# moire_v1_6.net
KiCad netlist of a schematic drawn in EAGLE
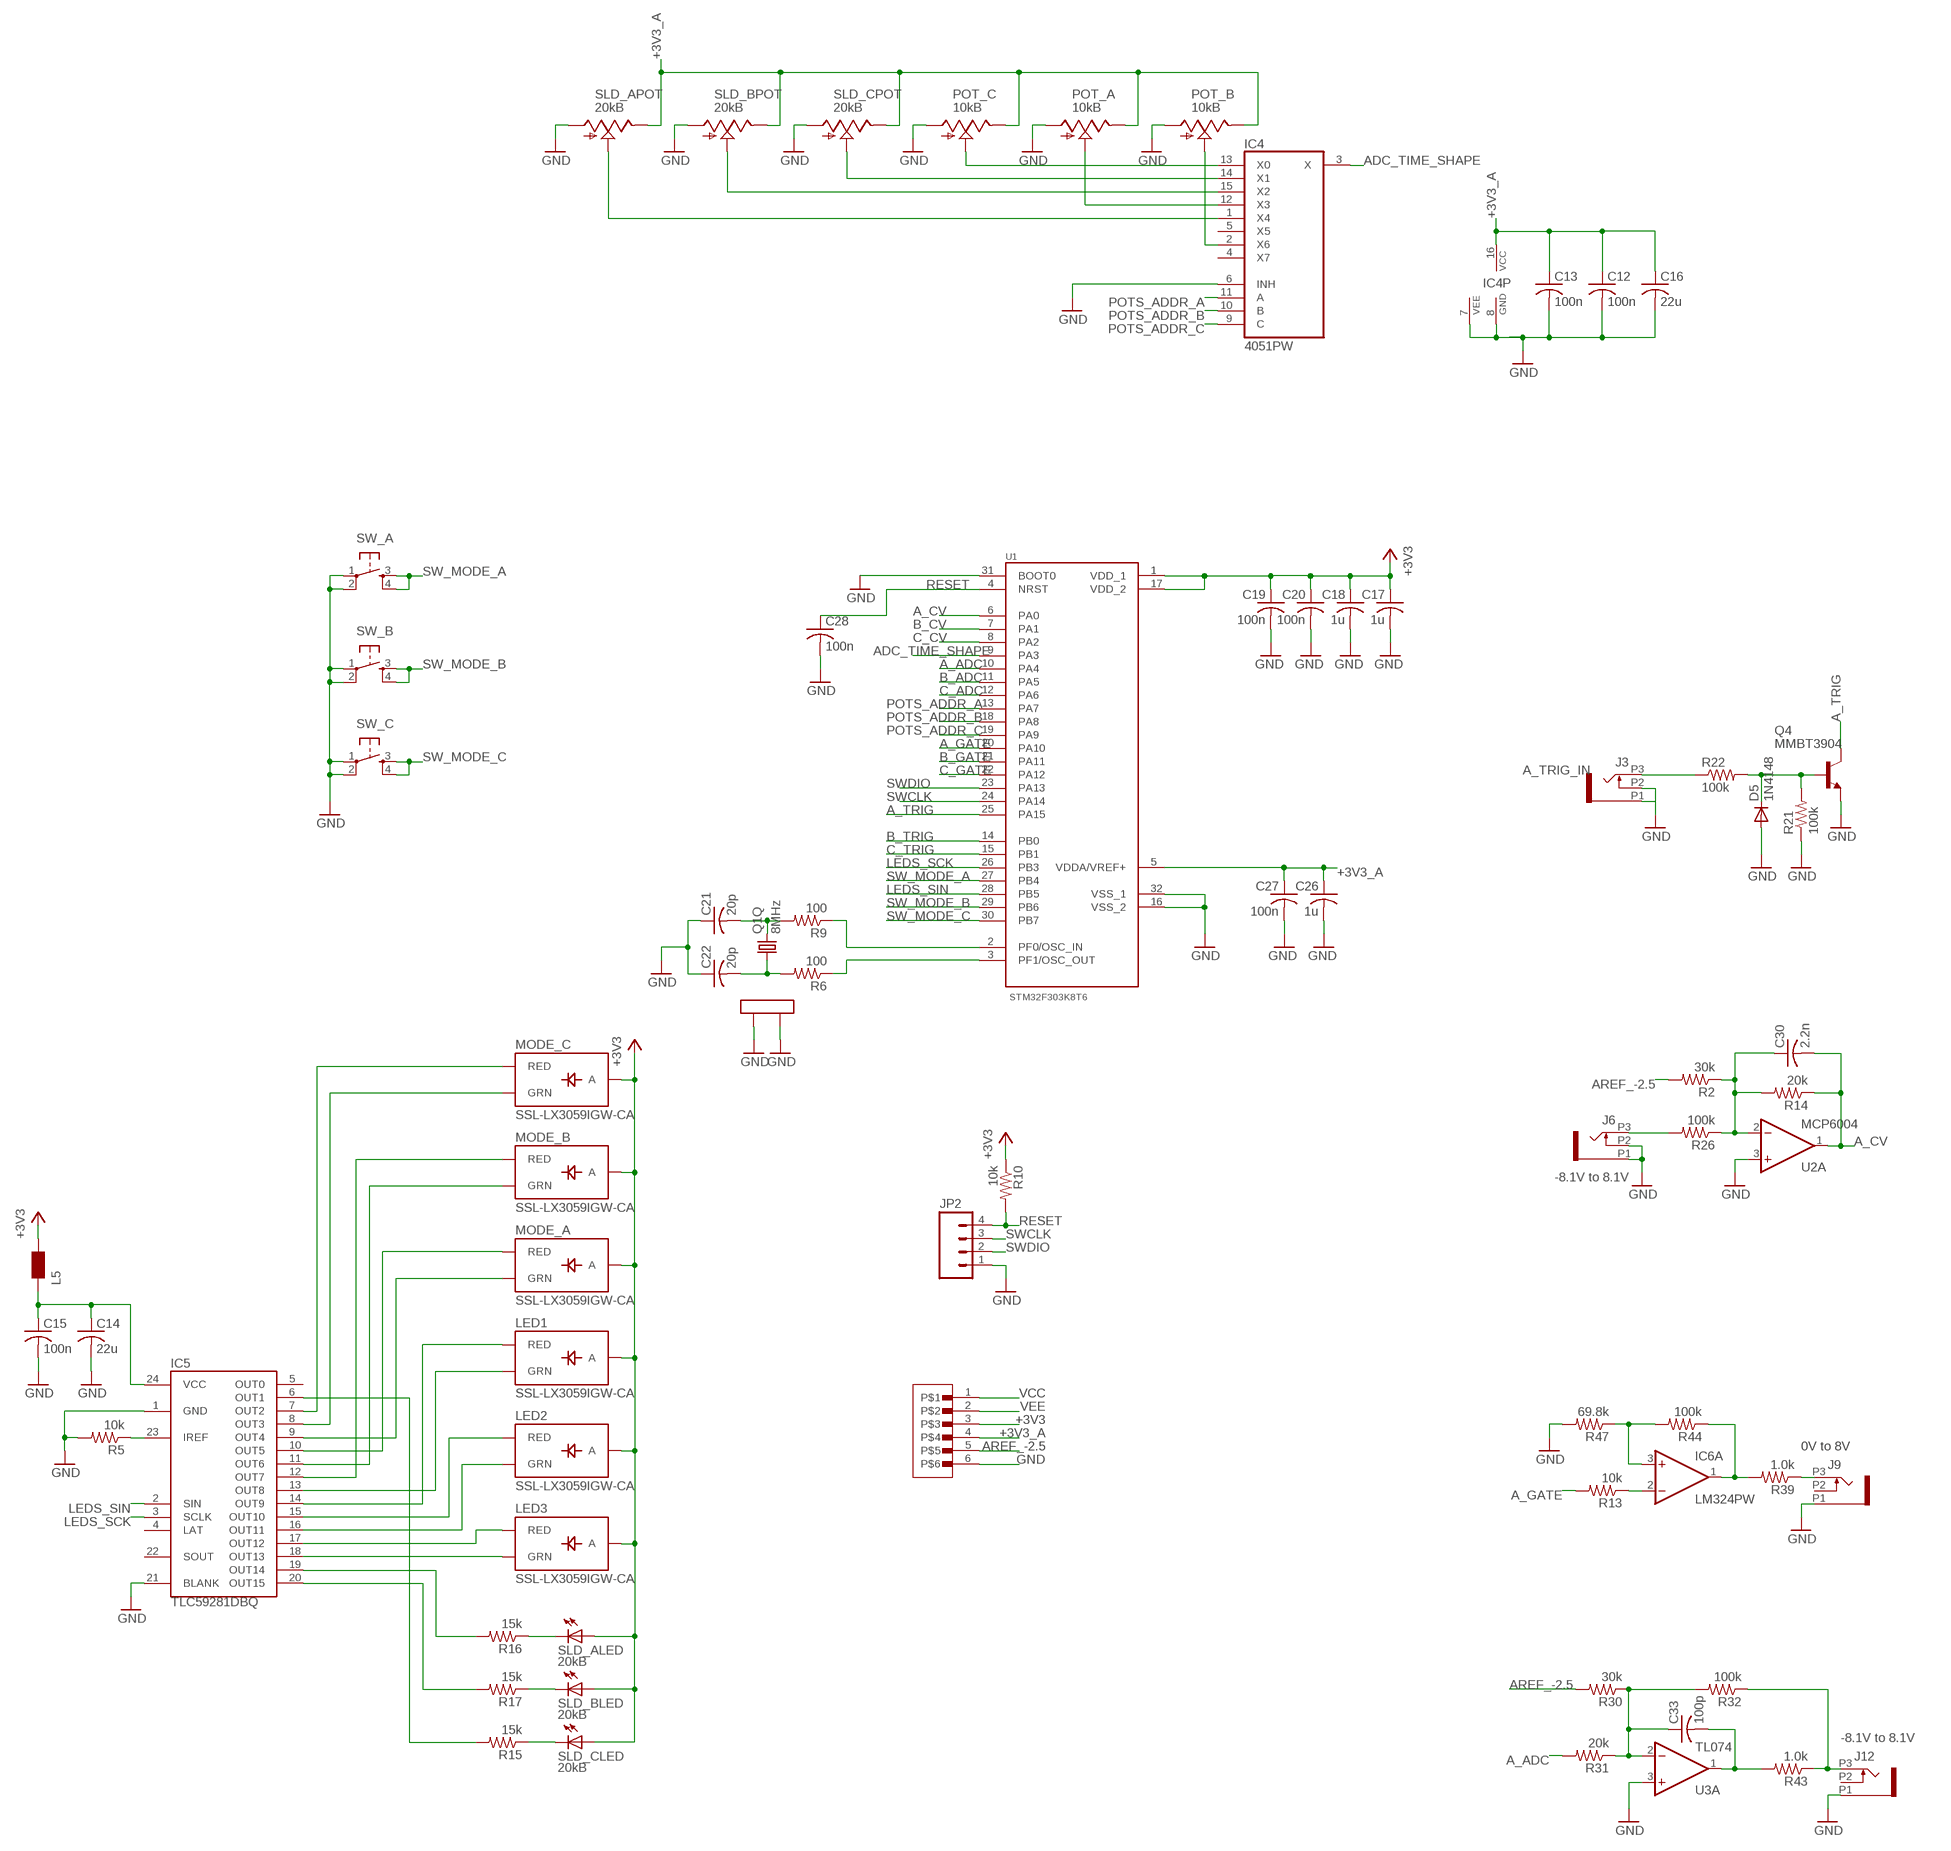
[diagram p0: schematic, sheet 1, part 1 of 2]
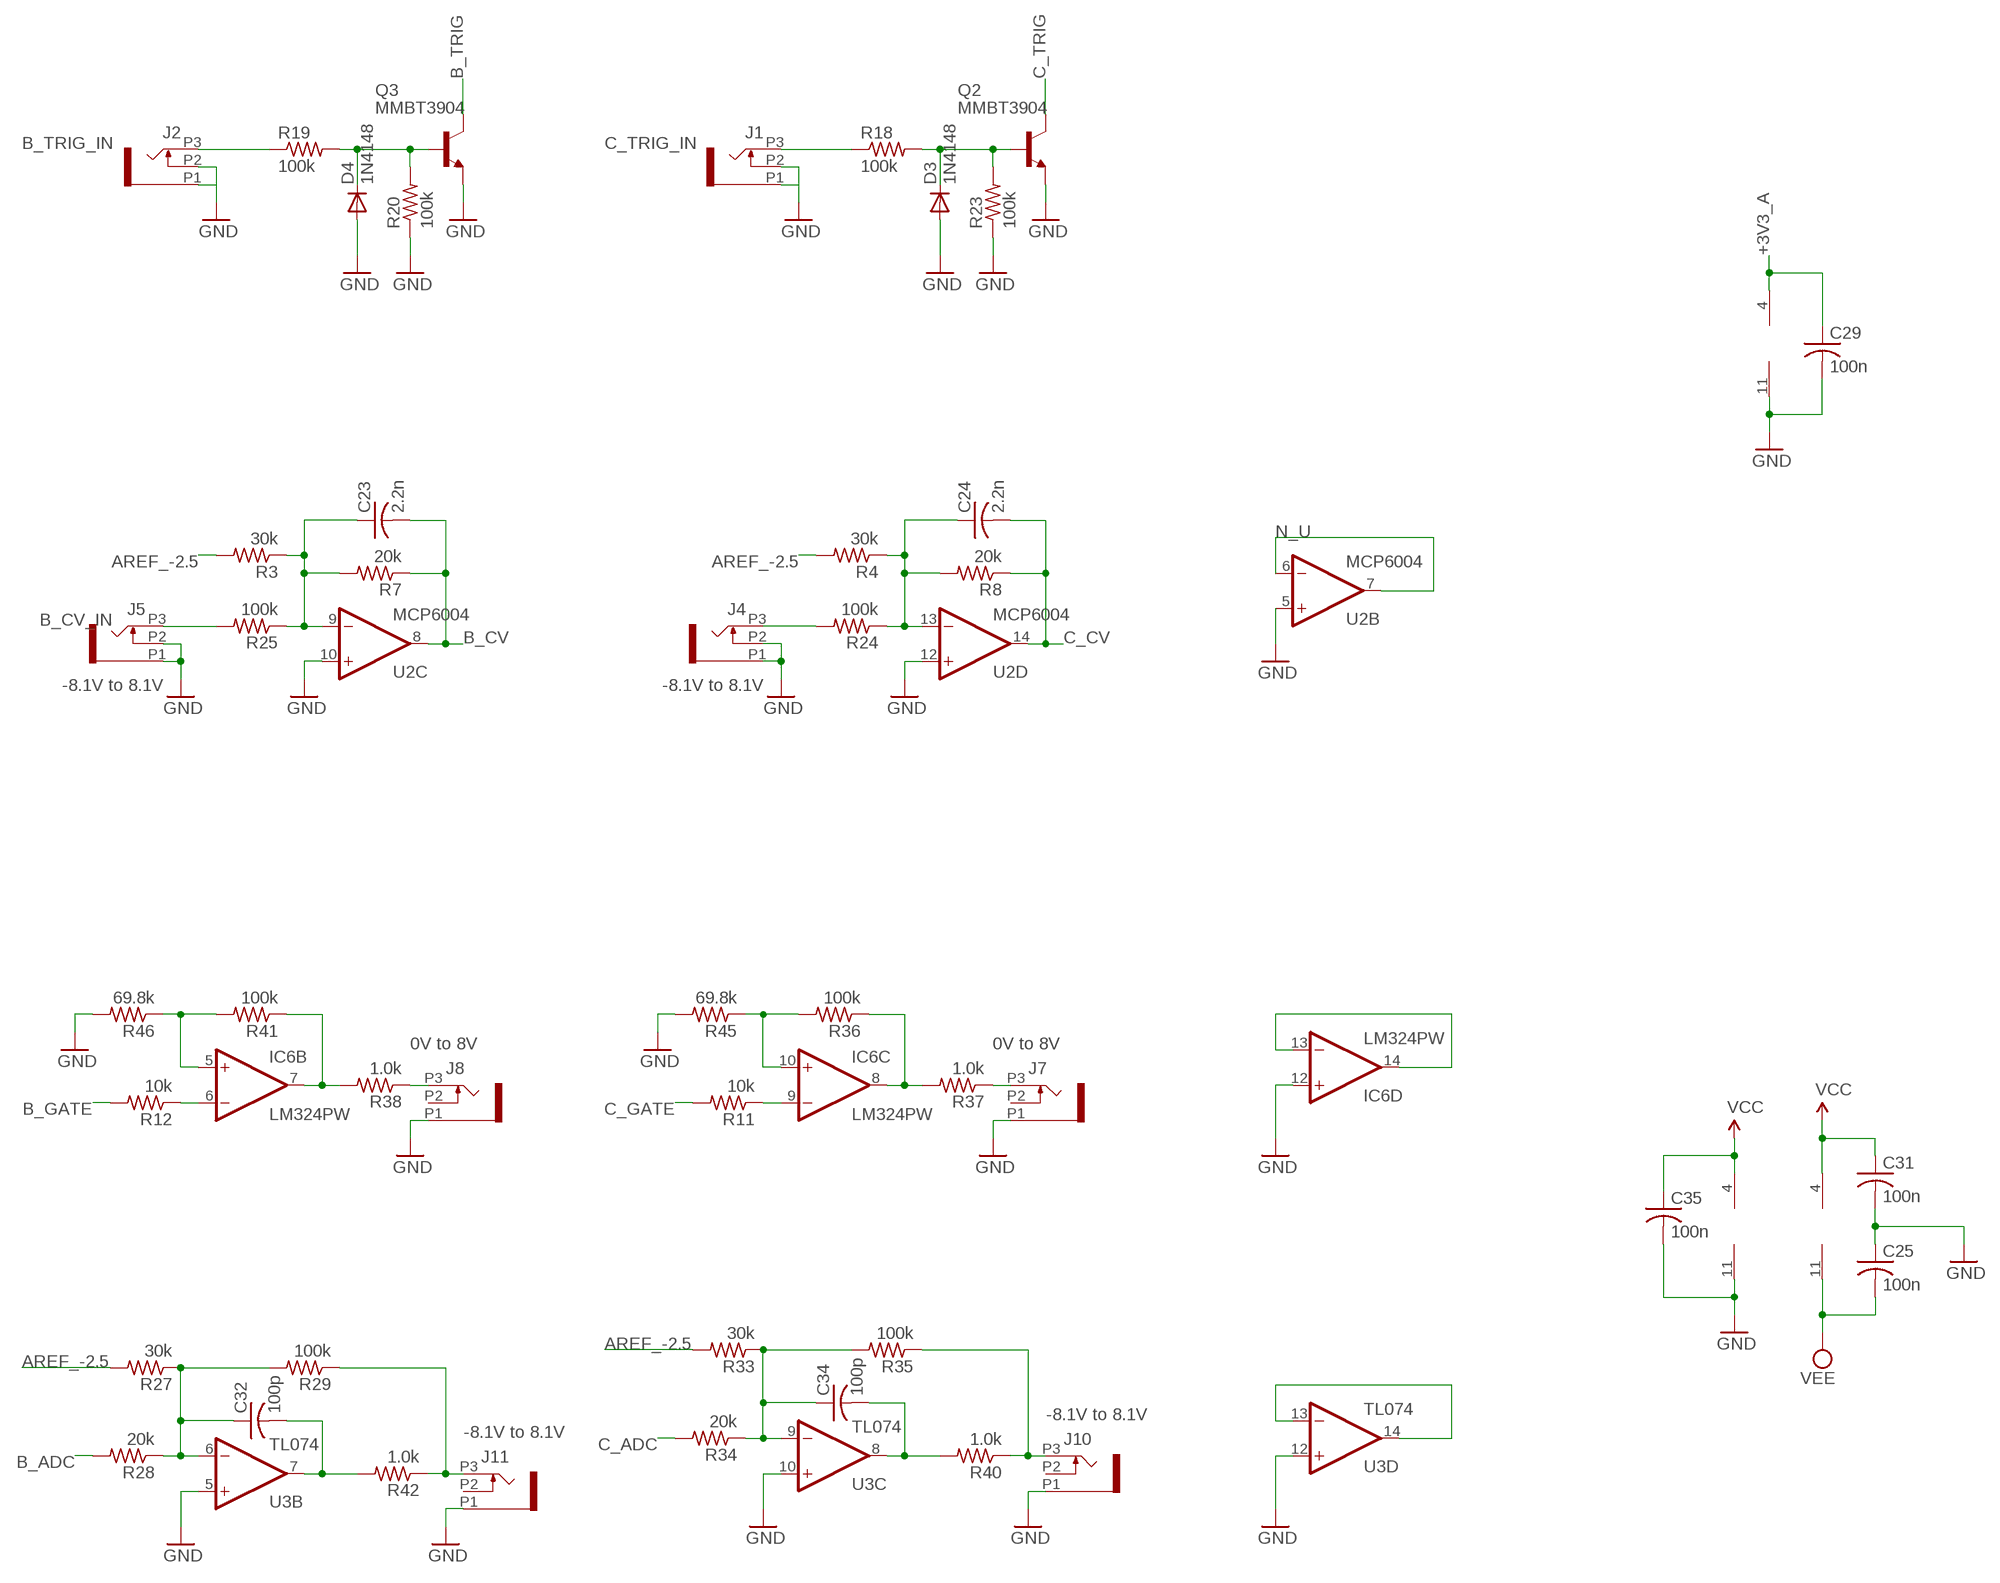
[diagram p1: schematic, sheet 1, part 2 of 2]
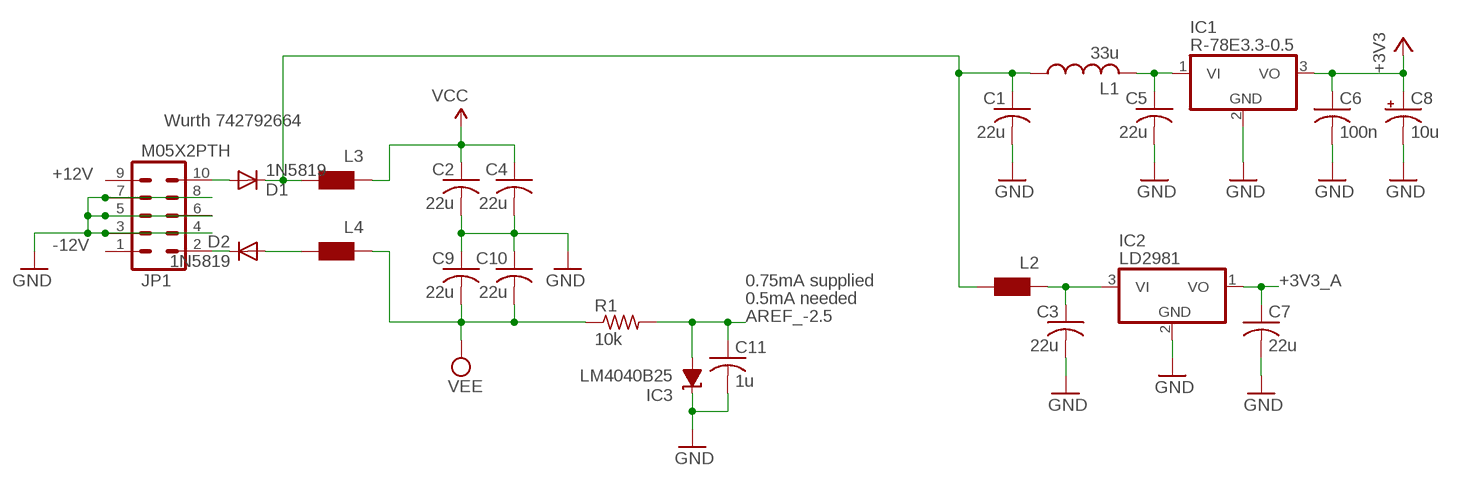
[diagram p2: schematic, sheet 2]

(export (version "E")
  (design (tool "Eeschema 10.0.6"))
  (components
    (comp (ref "C12")
      (value "100n")
      (footprint "eagle-import:RCL_C0603")
      (libsource (lib "eagle-import") (part "RCL_C-USC0603"))
    )
    (comp (ref "C13")
      (value "100n")
      (footprint "eagle-import:RCL_C0603")
      (libsource (lib "eagle-import") (part "RCL_C-USC0603"))
    )
    (comp (ref "C14")
      (value "22u")
      (footprint "eagle-import:RCL_C1206")
      (libsource (lib "eagle-import") (part "RCL_C-USC1206"))
    )
    (comp (ref "C15")
      (value "100n")
      (footprint "eagle-import:RCL_C0603")
      (libsource (lib "eagle-import") (part "RCL_C-USC0603"))
    )
    (comp (ref "C16")
      (value "22u")
      (footprint "eagle-import:RCL_C1206")
      (libsource (lib "eagle-import") (part "RCL_C-USC1206"))
    )
    (comp (ref "C17")
      (value "1u")
      (footprint "eagle-import:RCL_C0603")
      (libsource (lib "eagle-import") (part "RCL_C-USC0603"))
    )
    (comp (ref "C18")
      (value "1u")
      (footprint "eagle-import:RCL_C0603")
      (libsource (lib "eagle-import") (part "RCL_C-USC0603"))
    )
    (comp (ref "C19")
      (value "100n")
      (footprint "eagle-import:RCL_C0603")
      (libsource (lib "eagle-import") (part "RCL_C-USC0603"))
    )
    (comp (ref "C20")
      (value "100n")
      (footprint "eagle-import:RCL_C0603")
      (libsource (lib "eagle-import") (part "RCL_C-USC0603"))
    )
    (comp (ref "C21")
      (value "20p")
      (footprint "eagle-import:RCL_C0603")
      (libsource (lib "eagle-import") (part "RCL_C-USC0603"))
    )
    (comp (ref "C22")
      (value "20p")
      (footprint "eagle-import:RCL_C0603")
      (libsource (lib "eagle-import") (part "RCL_C-USC0603"))
    )
    (comp (ref "C23")
      (value "2.2n")
      (footprint "eagle-import:RCL_C0603")
      (libsource (lib "eagle-import") (part "RCL_C-USC0603"))
    )
    (comp (ref "C24")
      (value "2.2n")
      (footprint "eagle-import:RCL_C0603")
      (libsource (lib "eagle-import") (part "RCL_C-USC0603"))
    )
    (comp (ref "C25")
      (value "100n")
      (footprint "eagle-import:RCL_C0603")
      (libsource (lib "eagle-import") (part "RCL_C-USC0603"))
    )
    (comp (ref "C26")
      (value "1u")
      (footprint "eagle-import:RCL_C0603")
      (libsource (lib "eagle-import") (part "RCL_C-USC0603"))
    )
    (comp (ref "C27")
      (value "100n")
      (footprint "eagle-import:RCL_C0603")
      (libsource (lib "eagle-import") (part "RCL_C-USC0603"))
    )
    (comp (ref "C28")
      (value "100n")
      (footprint "eagle-import:RCL_C0603")
      (libsource (lib "eagle-import") (part "RCL_C-USC0603"))
    )
    (comp (ref "C29")
      (value "100n")
      (footprint "eagle-import:RCL_C0603")
      (libsource (lib "eagle-import") (part "RCL_C-USC0603"))
    )
    (comp (ref "C30")
      (value "2.2n")
      (footprint "eagle-import:RCL_C0603")
      (libsource (lib "eagle-import") (part "RCL_C-USC0603"))
    )
    (comp (ref "C31")
      (value "100n")
      (footprint "eagle-import:RCL_C0603")
      (libsource (lib "eagle-import") (part "RCL_C-USC0603"))
    )
    (comp (ref "C32")
      (value "100p")
      (footprint "eagle-import:RCL_C0603")
      (libsource (lib "eagle-import") (part "RCL_C-USC0603"))
    )
    (comp (ref "C33")
      (value "100p")
      (footprint "eagle-import:RCL_C0603")
      (libsource (lib "eagle-import") (part "RCL_C-USC0603"))
    )
    (comp (ref "C34")
      (value "100p")
      (footprint "eagle-import:RCL_C0603")
      (libsource (lib "eagle-import") (part "RCL_C-USC0603"))
    )
    (comp (ref "C35")
      (value "100n")
      (footprint "eagle-import:RCL_C0603")
      (libsource (lib "eagle-import") (part "RCL_C-USC0603"))
    )
    (comp (ref "D3")
      (value "1N4148")
      (footprint "eagle-import:SOD523")
      (libsource (lib "eagle-import") (part "DIODE-SOD523"))
    )
    (comp (ref "D4")
      (value "1N4148")
      (footprint "eagle-import:SOD523")
      (libsource (lib "eagle-import") (part "DIODE-SOD523"))
    )
    (comp (ref "D5")
      (value "1N4148")
      (footprint "eagle-import:SOD523")
      (libsource (lib "eagle-import") (part "DIODE-SOD523"))
    )
    (comp (ref "IC4")
      (value "4051PW")
      (footprint "eagle-import:TSSOP16_065")
      (libsource (lib "eagle-import") (part "4051PW"))
    )
    (comp (ref "IC5")
      (value "TLC59281DBQ")
      (footprint "eagle-import:TSSOP24_0635")
      (libsource (lib "eagle-import") (part "TLC59281DBQ"))
    )
    (comp (ref "IC6")
      (value "LM324PW")
      (footprint "eagle-import:TSSOP14_065")
      (libsource (lib "eagle-import") (part "TL074PW"))
    )
    (comp (ref "J1")
      (value "PJ301_THONKICONN6")
      (footprint "eagle-import:WQP_PJ_301M6")
      (libsource (lib "eagle-import") (part "PJ301_THONKICONN6"))
    )
    (comp (ref "J2")
      (value "PJ301_THONKICONN6")
      (footprint "eagle-import:WQP_PJ_301M6")
      (libsource (lib "eagle-import") (part "PJ301_THONKICONN6"))
    )
    (comp (ref "J3")
      (value "PJ301_THONKICONN6")
      (footprint "eagle-import:WQP_PJ_301M6")
      (libsource (lib "eagle-import") (part "PJ301_THONKICONN6"))
    )
    (comp (ref "J4")
      (value "PJ301_THONKICONN6")
      (footprint "eagle-import:WQP_PJ_301M6")
      (libsource (lib "eagle-import") (part "PJ301_THONKICONN6"))
    )
    (comp (ref "J5")
      (value "PJ301_THONKICONN6")
      (footprint "eagle-import:WQP_PJ_301M6")
      (libsource (lib "eagle-import") (part "PJ301_THONKICONN6"))
    )
    (comp (ref "J6")
      (value "PJ301_THONKICONN6")
      (footprint "eagle-import:WQP_PJ_301M6")
      (libsource (lib "eagle-import") (part "PJ301_THONKICONN6"))
    )
    (comp (ref "J7")
      (value "PJ301_THONKICONN6")
      (footprint "eagle-import:WQP_PJ_301M6")
      (libsource (lib "eagle-import") (part "PJ301_THONKICONN6"))
    )
    (comp (ref "J8")
      (value "PJ301_THONKICONN6")
      (footprint "eagle-import:WQP_PJ_301M6")
      (libsource (lib "eagle-import") (part "PJ301_THONKICONN6"))
    )
    (comp (ref "J9")
      (value "PJ301_THONKICONN6")
      (footprint "eagle-import:WQP_PJ_301M6")
      (libsource (lib "eagle-import") (part "PJ301_THONKICONN6"))
    )
    (comp (ref "J10")
      (value "PJ301_THONKICONN6")
      (footprint "eagle-import:WQP_PJ_301M6")
      (libsource (lib "eagle-import") (part "PJ301_THONKICONN6"))
    )
    (comp (ref "J11")
      (value "PJ301_THONKICONN6")
      (footprint "eagle-import:WQP_PJ_301M6")
      (libsource (lib "eagle-import") (part "PJ301_THONKICONN6"))
    )
    (comp (ref "J12")
      (value "PJ301_THONKICONN6")
      (footprint "eagle-import:WQP_PJ_301M6")
      (libsource (lib "eagle-import") (part "PJ301_THONKICONN6"))
    )
    (comp (ref "JP2")
      (value "M04PTH")
      (footprint "eagle-import:1X04")
      (libsource (lib "eagle-import") (part "M04PTH"))
    )
    (comp (ref "L5")
      (value "WE-CBF_0603")
      (footprint "eagle-import:0603")
      (libsource (lib "eagle-import") (part "WE-CBF_0603"))
    )
    (comp (ref "LED1")
      (value "SSL-LX3059IGW-CA")
      (footprint "eagle-import:LED-BICOLOR-THROUGHHOLE-LUMEX")
      (libsource (lib "eagle-import") (part "LED-BICOLOR-THROUGHHOLE-CA"))
    )
    (comp (ref "LED2")
      (value "SSL-LX3059IGW-CA")
      (footprint "eagle-import:LED-BICOLOR-THROUGHHOLE-LUMEX")
      (libsource (lib "eagle-import") (part "LED-BICOLOR-THROUGHHOLE-CA"))
    )
    (comp (ref "LED3")
      (value "SSL-LX3059IGW-CA")
      (footprint "eagle-import:LED-BICOLOR-THROUGHHOLE-LUMEX")
      (libsource (lib "eagle-import") (part "LED-BICOLOR-THROUGHHOLE-CA"))
    )
    (comp (ref "MODE_A")
      (value "SSL-LX3059IGW-CA")
      (footprint "eagle-import:LED-BICOLOR-THROUGHHOLE-LUMEX")
      (libsource (lib "eagle-import") (part "LED-BICOLOR-THROUGHHOLE-CA"))
    )
    (comp (ref "MODE_B")
      (value "SSL-LX3059IGW-CA")
      (footprint "eagle-import:LED-BICOLOR-THROUGHHOLE-LUMEX")
      (libsource (lib "eagle-import") (part "LED-BICOLOR-THROUGHHOLE-CA"))
    )
    (comp (ref "MODE_C")
      (value "SSL-LX3059IGW-CA")
      (footprint "eagle-import:LED-BICOLOR-THROUGHHOLE-LUMEX")
      (libsource (lib "eagle-import") (part "LED-BICOLOR-THROUGHHOLE-CA"))
    )
    (comp (ref "POT_A")
      (value "10kB")
      (footprint "eagle-import:ALPS_POT_VERTICAL")
      (libsource (lib "eagle-import") (part "POT_USVERTICAL"))
    )
    (comp (ref "POT_B")
      (value "10kB")
      (footprint "eagle-import:ALPS_POT_VERTICAL")
      (libsource (lib "eagle-import") (part "POT_USVERTICAL"))
    )
    (comp (ref "POT_C")
      (value "10kB")
      (footprint "eagle-import:ALPS_POT_VERTICAL")
      (libsource (lib "eagle-import") (part "POT_USVERTICAL"))
    )
    (comp (ref "Q1")
      (value "8MHz")
      (footprint "eagle-import:CTS406")
      (libsource (lib "eagle-import") (part "CRYSTAL"))
    )
    (comp (ref "Q2")
      (value "MMBT3904")
      (footprint "eagle-import:SOT23-BEC")
      (libsource (lib "eagle-import") (part "-NPN-SOT23-BECMMBT3904LT1"))
    )
    (comp (ref "Q3")
      (value "MMBT3904")
      (footprint "eagle-import:SOT23-BEC")
      (libsource (lib "eagle-import") (part "-NPN-SOT23-BECMMBT3904LT1"))
    )
    (comp (ref "Q4")
      (value "MMBT3904")
      (footprint "eagle-import:SOT23-BEC")
      (libsource (lib "eagle-import") (part "-NPN-SOT23-BECMMBT3904LT1"))
    )
    (comp (ref "R2")
      (value "30k")
      (footprint "eagle-import:RCL_R0603")
      (libsource (lib "eagle-import") (part "RCL_R-US_R0603"))
    )
    (comp (ref "R3")
      (value "30k")
      (footprint "eagle-import:RCL_R0603")
      (libsource (lib "eagle-import") (part "RCL_R-US_R0603"))
    )
    (comp (ref "R4")
      (value "30k")
      (footprint "eagle-import:RCL_R0603")
      (libsource (lib "eagle-import") (part "RCL_R-US_R0603"))
    )
    (comp (ref "R5")
      (value "10k")
      (footprint "eagle-import:RCL_R0603")
      (libsource (lib "eagle-import") (part "RCL_R-US_R0603"))
    )
    (comp (ref "R6")
      (value "100")
      (footprint "eagle-import:RCL_R0603")
      (libsource (lib "eagle-import") (part "RCL_R-US_R0603"))
    )
    (comp (ref "R7")
      (value "20k")
      (footprint "eagle-import:RCL_R0603")
      (libsource (lib "eagle-import") (part "RCL_R-US_R0603"))
    )
    (comp (ref "R8")
      (value "20k")
      (footprint "eagle-import:RCL_R0603")
      (libsource (lib "eagle-import") (part "RCL_R-US_R0603"))
    )
    (comp (ref "R9")
      (value "100")
      (footprint "eagle-import:RCL_R0603")
      (libsource (lib "eagle-import") (part "RCL_R-US_R0603"))
    )
    (comp (ref "R10")
      (value "10k")
      (footprint "eagle-import:RCL_R0603")
      (libsource (lib "eagle-import") (part "RCL_R-US_R0603"))
    )
    (comp (ref "R11")
      (value "10k")
      (footprint "eagle-import:RCL_R0603")
      (libsource (lib "eagle-import") (part "RCL_R-US_R0603"))
    )
    (comp (ref "R12")
      (value "10k")
      (footprint "eagle-import:RCL_R0603")
      (libsource (lib "eagle-import") (part "RCL_R-US_R0603"))
    )
    (comp (ref "R13")
      (value "10k")
      (footprint "eagle-import:RCL_R0603")
      (libsource (lib "eagle-import") (part "RCL_R-US_R0603"))
    )
    (comp (ref "R14")
      (value "20k")
      (footprint "eagle-import:RCL_R0603")
      (libsource (lib "eagle-import") (part "RCL_R-US_R0603"))
    )
    (comp (ref "R15")
      (value "15k")
      (footprint "eagle-import:RCL_R0603")
      (libsource (lib "eagle-import") (part "RCL_R-US_R0603"))
    )
    (comp (ref "R16")
      (value "15k")
      (footprint "eagle-import:RCL_R0603")
      (libsource (lib "eagle-import") (part "RCL_R-US_R0603"))
    )
    (comp (ref "R17")
      (value "15k")
      (footprint "eagle-import:RCL_R0603")
      (libsource (lib "eagle-import") (part "RCL_R-US_R0603"))
    )
    (comp (ref "R18")
      (value "100k")
      (footprint "eagle-import:RCL_R0603")
      (libsource (lib "eagle-import") (part "RCL_R-US_R0603"))
    )
    (comp (ref "R19")
      (value "100k")
      (footprint "eagle-import:RCL_R0603")
      (libsource (lib "eagle-import") (part "RCL_R-US_R0603"))
    )
    (comp (ref "R20")
      (value "100k")
      (footprint "eagle-import:RCL_R0603")
      (libsource (lib "eagle-import") (part "RCL_R-US_R0603"))
    )
    (comp (ref "R21")
      (value "100k")
      (footprint "eagle-import:RCL_R0603")
      (libsource (lib "eagle-import") (part "RCL_R-US_R0603"))
    )
    (comp (ref "R22")
      (value "100k")
      (footprint "eagle-import:RCL_R0603")
      (libsource (lib "eagle-import") (part "RCL_R-US_R0603"))
    )
    (comp (ref "R23")
      (value "100k")
      (footprint "eagle-import:RCL_R0603")
      (libsource (lib "eagle-import") (part "RCL_R-US_R0603"))
    )
    (comp (ref "R24")
      (value "100k")
      (footprint "eagle-import:RCL_R0603")
      (libsource (lib "eagle-import") (part "RCL_R-US_R0603"))
    )
    (comp (ref "R25")
      (value "100k")
      (footprint "eagle-import:RCL_R0603")
      (libsource (lib "eagle-import") (part "RCL_R-US_R0603"))
    )
    (comp (ref "R26")
      (value "100k")
      (footprint "eagle-import:RCL_R0603")
      (libsource (lib "eagle-import") (part "RCL_R-US_R0603"))
    )
    (comp (ref "R27")
      (value "30k")
      (footprint "eagle-import:RCL_R0603")
      (libsource (lib "eagle-import") (part "RCL_R-US_R0603"))
    )
    (comp (ref "R28")
      (value "20k")
      (footprint "eagle-import:RCL_R0603")
      (libsource (lib "eagle-import") (part "RCL_R-US_R0603"))
    )
    (comp (ref "R29")
      (value "100k")
      (footprint "eagle-import:RCL_R0603")
      (libsource (lib "eagle-import") (part "RCL_R-US_R0603"))
    )
    (comp (ref "R30")
      (value "30k")
      (footprint "eagle-import:RCL_R0603")
      (libsource (lib "eagle-import") (part "RCL_R-US_R0603"))
    )
    (comp (ref "R31")
      (value "20k")
      (footprint "eagle-import:RCL_R0603")
      (libsource (lib "eagle-import") (part "RCL_R-US_R0603"))
    )
    (comp (ref "R32")
      (value "100k")
      (footprint "eagle-import:RCL_R0603")
      (libsource (lib "eagle-import") (part "RCL_R-US_R0603"))
    )
    (comp (ref "R33")
      (value "30k")
      (footprint "eagle-import:RCL_R0603")
      (libsource (lib "eagle-import") (part "RCL_R-US_R0603"))
    )
    (comp (ref "R34")
      (value "20k")
      (footprint "eagle-import:RCL_R0603")
      (libsource (lib "eagle-import") (part "RCL_R-US_R0603"))
    )
    (comp (ref "R35")
      (value "100k")
      (footprint "eagle-import:RCL_R0603")
      (libsource (lib "eagle-import") (part "RCL_R-US_R0603"))
    )
    (comp (ref "R36")
      (value "100k")
      (footprint "eagle-import:RCL_R0603")
      (libsource (lib "eagle-import") (part "RCL_R-US_R0603"))
    )
    (comp (ref "R37")
      (value "1.0k")
      (footprint "eagle-import:RCL_R0603")
      (libsource (lib "eagle-import") (part "RCL_R-US_R0603"))
    )
    (comp (ref "R38")
      (value "1.0k")
      (footprint "eagle-import:RCL_R0603")
      (libsource (lib "eagle-import") (part "RCL_R-US_R0603"))
    )
    (comp (ref "R39")
      (value "1.0k")
      (footprint "eagle-import:RCL_R0603")
      (libsource (lib "eagle-import") (part "RCL_R-US_R0603"))
    )
    (comp (ref "R40")
      (value "1.0k")
      (footprint "eagle-import:RCL_R0603")
      (libsource (lib "eagle-import") (part "RCL_R-US_R0603"))
    )
    (comp (ref "R41")
      (value "100k")
      (footprint "eagle-import:RCL_R0603")
      (libsource (lib "eagle-import") (part "RCL_R-US_R0603"))
    )
    (comp (ref "R42")
      (value "1.0k")
      (footprint "eagle-import:RCL_R0603")
      (libsource (lib "eagle-import") (part "RCL_R-US_R0603"))
    )
    (comp (ref "R43")
      (value "1.0k")
      (footprint "eagle-import:RCL_R0603")
      (libsource (lib "eagle-import") (part "RCL_R-US_R0603"))
    )
    (comp (ref "R44")
      (value "100k")
      (footprint "eagle-import:RCL_R0603")
      (libsource (lib "eagle-import") (part "RCL_R-US_R0603"))
    )
    (comp (ref "R45")
      (value "69.8k")
      (footprint "eagle-import:RCL_R0603")
      (libsource (lib "eagle-import") (part "RCL_R-US_R0603"))
    )
    (comp (ref "R46")
      (value "69.8k")
      (footprint "eagle-import:RCL_R0603")
      (libsource (lib "eagle-import") (part "RCL_R-US_R0603"))
    )
    (comp (ref "R47")
      (value "69.8k")
      (footprint "eagle-import:RCL_R0603")
      (libsource (lib "eagle-import") (part "RCL_R-US_R0603"))
    )
    (comp (ref "SLD_A")
      (value "20kB")
      (footprint "eagle-import:BOURNS_SLIDER")
      (libsource (lib "eagle-import") (part "BOURNS_SLIDER"))
    )
    (comp (ref "SLD_B")
      (value "20kB")
      (footprint "eagle-import:BOURNS_SLIDER")
      (libsource (lib "eagle-import") (part "BOURNS_SLIDER"))
    )
    (comp (ref "SLD_C")
      (value "20kB")
      (footprint "eagle-import:BOURNS_SLIDER")
      (libsource (lib "eagle-import") (part "BOURNS_SLIDER"))
    )
    (comp (ref "SW_A")
      (value "TAC_SWITCHPTH")
      (footprint "eagle-import:TACTILE-PTH")
      (libsource (lib "eagle-import") (part "TAC_SWITCHPTH"))
    )
    (comp (ref "SW_B")
      (value "TAC_SWITCHPTH")
      (footprint "eagle-import:TACTILE-PTH")
      (libsource (lib "eagle-import") (part "TAC_SWITCHPTH"))
    )
    (comp (ref "SW_C")
      (value "TAC_SWITCHPTH")
      (footprint "eagle-import:TACTILE-PTH")
      (libsource (lib "eagle-import") (part "TAC_SWITCHPTH"))
    )
    (comp (ref "U$1")
      (value "1X6-SMD-TESTPAD")
      (footprint "eagle-import:6X1-SMD-TESTPAD")
      (libsource (lib "eagle-import") (part "1X6-SMD-TESTPAD"))
    )
    (comp (ref "U1")
      (value "STM32F303K8T6")
      (footprint "eagle-import:QFP80P900X900X160-32N")
      (fields (field (name "MF") "STMicroelectronics"))
      (libsource (lib "eagle-import") (part "STM32F303K8T6"))
    )
    (comp (ref "U2")
      (value "MCP6004")
      (footprint "eagle-import:SO14")
      (libsource (lib "eagle-import") (part "MCP6004_SMD"))
    )
    (comp (ref "U3")
      (value "TL074")
      (footprint "eagle-import:SO14")
      (libsource (lib "eagle-import") (part "TL074_SMD"))
    )
    (comp (ref "C1")
      (value "22u")
      (footprint "eagle-import:RCL_C1206")
      (libsource (lib "eagle-import") (part "RCL_C-USC1206"))
    )
    (comp (ref "C2")
      (value "22u")
      (footprint "eagle-import:RCL_C1206")
      (libsource (lib "eagle-import") (part "RCL_C-USC1206"))
    )
    (comp (ref "C3")
      (value "22u")
      (footprint "eagle-import:RCL_C1206")
      (libsource (lib "eagle-import") (part "RCL_C-USC1206"))
    )
    (comp (ref "C4")
      (value "22u")
      (footprint "eagle-import:RCL_C1206")
      (libsource (lib "eagle-import") (part "RCL_C-USC1206"))
    )
    (comp (ref "C5")
      (value "22u")
      (footprint "eagle-import:RCL_C1206")
      (libsource (lib "eagle-import") (part "RCL_C-USC1206"))
    )
    (comp (ref "C6")
      (value "100n")
      (footprint "eagle-import:RCL_C0603")
      (libsource (lib "eagle-import") (part "RCL_C-USC0603"))
    )
    (comp (ref "C7")
      (value "22u")
      (footprint "eagle-import:RCL_C1206")
      (libsource (lib "eagle-import") (part "RCL_C-USC1206"))
    )
    (comp (ref "C8")
      (value "10u")
      (footprint "eagle-import:RCL_PANASONIC_A")
      (libsource (lib "eagle-import") (part "RCL_CPOL-USA"))
    )
    (comp (ref "C9")
      (value "22u")
      (footprint "eagle-import:RCL_C1206")
      (libsource (lib "eagle-import") (part "RCL_C-USC1206"))
    )
    (comp (ref "C10")
      (value "22u")
      (footprint "eagle-import:RCL_C1206")
      (libsource (lib "eagle-import") (part "RCL_C-USC1206"))
    )
    (comp (ref "C11")
      (value "1u")
      (footprint "eagle-import:RCL_C0603")
      (libsource (lib "eagle-import") (part "RCL_C-USC0603"))
    )
    (comp (ref "D1")
      (value "1N5819")
      (footprint "eagle-import:SOD123")
      (libsource (lib "eagle-import") (part "DIODE-SOD123"))
    )
    (comp (ref "D2")
      (value "1N5819")
      (footprint "eagle-import:SOD123")
      (libsource (lib "eagle-import") (part "DIODE-SOD123"))
    )
    (comp (ref "IC1")
      (value "R-78E3.3-0.5")
      (footprint "eagle-import:WE78")
      (libsource (lib "eagle-import") (part "WE173950378"))
    )
    (comp (ref "IC2")
      (value "LD2981")
      (footprint "eagle-import:SOT89")
      (libsource (lib "eagle-import") (part "LD2981ABU"))
    )
    (comp (ref "IC3")
      (value "LM4040B25")
      (footprint "eagle-import:DBZ_R-PDSO-G3")
      (libsource (lib "eagle-import") (part "LM4041DBZB12"))
    )
    (comp (ref "JP1")
      (value "M05X2PTH")
      (footprint "eagle-import:2X5-PTH")
      (libsource (lib "eagle-import") (part "M05X2PTH"))
    )
    (comp (ref "L1")
      (value "33u")
      (footprint "eagle-import:L2012C")
      (libsource (lib "eagle-import") (part "L-USL2012C"))
    )
    (comp (ref "L2")
      (value "WE-CBF_0603")
      (footprint "eagle-import:0603")
      (libsource (lib "eagle-import") (part "WE-CBF_0603"))
    )
    (comp (ref "L3")
      (value "WE-CBF_0603")
      (footprint "eagle-import:0603")
      (libsource (lib "eagle-import") (part "WE-CBF_0603"))
    )
    (comp (ref "L4")
      (value "WE-CBF_0603")
      (footprint "eagle-import:0603")
      (libsource (lib "eagle-import") (part "WE-CBF_0603"))
    )
    (comp (ref "R1")
      (value "10k")
      (footprint "eagle-import:RCL_R0603")
      (libsource (lib "eagle-import") (part "RCL_R-US_R0603"))
    )
  )
  (nets
    (net (code "1") (name "+3V3") (class "Default")
      (node (ref "C17") (pin "1") (pinfunction "1_1") (pintype "passive"))
      (node (ref "C18") (pin "1") (pinfunction "1_1") (pintype "passive"))
      (node (ref "C19") (pin "1") (pinfunction "1_1") (pintype "passive"))
      (node (ref "C20") (pin "1") (pinfunction "1_1") (pintype "passive"))
      (node (ref "C6") (pin "1") (pinfunction "1_1") (pintype "passive"))
      (node (ref "C8") (pin "+") (pinfunction "+_+") (pintype "passive"))
      (node (ref "IC1") (pin "3") (pinfunction "VO_3") (pintype "passive"))
      (node (ref "L5") (pin "2") (pinfunction "2_2") (pintype "passive"))
      (node (ref "LED1") (pin "A") (pinfunction "A_A") (pintype "bidirectional"))
      (node (ref "LED2") (pin "A") (pinfunction "A_A") (pintype "bidirectional"))
      (node (ref "LED3") (pin "A") (pinfunction "A_A") (pintype "bidirectional"))
      (node (ref "MODE_A") (pin "A") (pinfunction "A_A") (pintype "bidirectional"))
      (node (ref "MODE_B") (pin "A") (pinfunction "A_A") (pintype "bidirectional"))
      (node (ref "MODE_C") (pin "A") (pinfunction "A_A") (pintype "bidirectional"))
      (node (ref "R10") (pin "1") (pinfunction "1_1") (pintype "passive"))
      (node (ref "SLD_A") (pin "B") (pinfunction "A_B") (pintype "passive"))
      (node (ref "SLD_B") (pin "B") (pinfunction "A_B") (pintype "passive"))
      (node (ref "SLD_C") (pin "B") (pinfunction "A_B") (pintype "passive"))
      (node (ref "U$1") (pin "3") (pinfunction "P$3_3") (pintype "bidirectional"))
      (node (ref "U1") (pin "1") (pinfunction "VDD_1_1") (pintype "power_in"))
      (node (ref "U1") (pin "17") (pinfunction "VDD_2_17") (pintype "power_in"))
    )
    (net (code "2") (name "+3V3_A") (class "Default")
      (node (ref "C12") (pin "1") (pinfunction "1_1") (pintype "passive"))
      (node (ref "C13") (pin "1") (pinfunction "1_1") (pintype "passive"))
      (node (ref "C16") (pin "1") (pinfunction "1_1") (pintype "passive"))
      (node (ref "C26") (pin "1") (pinfunction "1_1") (pintype "passive"))
      (node (ref "C27") (pin "1") (pinfunction "1_1") (pintype "passive"))
      (node (ref "C29") (pin "1") (pinfunction "1_1") (pintype "passive"))
      (node (ref "C7") (pin "1") (pinfunction "1_1") (pintype "passive"))
      (node (ref "IC2") (pin "1") (pinfunction "VO_1") (pintype "passive"))
      (node (ref "IC4") (pin "16") (pinfunction "VCC_16") (pintype "power_in"))
      (node (ref "POT_A") (pin "P$1") (pinfunction "E_P$1") (pintype "passive"))
      (node (ref "POT_B") (pin "P$1") (pinfunction "E_P$1") (pintype "passive"))
      (node (ref "POT_C") (pin "P$1") (pinfunction "E_P$1") (pintype "passive"))
      (node (ref "SLD_A") (pin "3") (pinfunction "E_3") (pintype "passive"))
      (node (ref "SLD_B") (pin "3") (pinfunction "E_3") (pintype "passive"))
      (node (ref "SLD_C") (pin "3") (pinfunction "E_3") (pintype "passive"))
      (node (ref "U$1") (pin "4") (pinfunction "P$4_4") (pintype "bidirectional"))
      (node (ref "U1") (pin "5") (pinfunction "VDDA/VREF+_5") (pintype "power_in"))
      (node (ref "U2") (pin "4") (pinfunction "V+_4") (pintype "power_in"))
    )
    (net (code "3") (name "+12V") (class "Default")
      (node (ref "D1") (pin "A") (pinfunction "A_A") (pintype "passive"))
      (node (ref "JP1") (pin "10") (pinfunction "10_10") (pintype "passive"))
      (node (ref "JP1") (pin "9") (pinfunction "9_9") (pintype "passive"))
    )
    (net (code "4") (name "-12V") (class "Default")
      (node (ref "D2") (pin "C") (pinfunction "C_C") (pintype "passive"))
      (node (ref "JP1") (pin "1") (pinfunction "1_1") (pintype "passive"))
      (node (ref "JP1") (pin "2") (pinfunction "2_2") (pintype "passive"))
    )
    (net (code "5") (name "ADC_TIME_SHAPE") (class "Default")
      (node (ref "IC4") (pin "3") (pinfunction "X_3") (pintype "bidirectional"))
      (node (ref "U1") (pin "9") (pinfunction "PA3_9") (pintype "bidirectional"))
    )
    (net (code "6") (name "AREF_-2.5") (class "Default")
      (node (ref "C11") (pin "1") (pinfunction "1_1") (pintype "passive"))
      (node (ref "IC3") (pin "2") (pinfunction "A_2") (pintype "passive"))
      (node (ref "R1") (pin "2") (pinfunction "2_2") (pintype "passive"))
      (node (ref "R2") (pin "2") (pinfunction "2_2") (pintype "passive"))
      (node (ref "R27") (pin "2") (pinfunction "2_2") (pintype "passive"))
      (node (ref "R3") (pin "2") (pinfunction "2_2") (pintype "passive"))
      (node (ref "R30") (pin "2") (pinfunction "2_2") (pintype "passive"))
      (node (ref "R33") (pin "2") (pinfunction "2_2") (pintype "passive"))
      (node (ref "R4") (pin "2") (pinfunction "2_2") (pintype "passive"))
      (node (ref "U$1") (pin "5") (pinfunction "P$5_5") (pintype "bidirectional"))
    )
    (net (code "7") (name "A_ADC") (class "Default")
      (node (ref "R31") (pin "2") (pinfunction "2_2") (pintype "passive"))
      (node (ref "U1") (pin "10") (pinfunction "PA4_10") (pintype "bidirectional"))
    )
    (net (code "8") (name "A_CV") (class "Default")
      (node (ref "C30") (pin "2") (pinfunction "2_2") (pintype "passive"))
      (node (ref "R14") (pin "1") (pinfunction "1_1") (pintype "passive"))
      (node (ref "U1") (pin "6") (pinfunction "PA0_6") (pintype "bidirectional"))
      (node (ref "U2") (pin "1") (pinfunction "OUT_1") (pintype "output"))
    )
    (net (code "9") (name "A_GATE") (class "Default")
      (node (ref "R13") (pin "2") (pinfunction "2_2") (pintype "passive"))
      (node (ref "U1") (pin "20") (pinfunction "PA10_20") (pintype "bidirectional"))
    )
    (net (code "10") (name "A_TRIG") (class "Default")
      (node (ref "Q4") (pin "C") (pinfunction "C_C") (pintype "passive"))
      (node (ref "U1") (pin "25") (pinfunction "PA15_25") (pintype "bidirectional"))
    )
    (net (code "11") (name "A_TRIG_IN") (class "Default")
      (node (ref "J3") (pin "P3") (pinfunction "3_P3") (pintype "passive"))
      (node (ref "R22") (pin "1") (pinfunction "1_1") (pintype "passive"))
    )
    (net (code "12") (name "B_ADC") (class "Default")
      (node (ref "R28") (pin "2") (pinfunction "2_2") (pintype "passive"))
      (node (ref "U1") (pin "11") (pinfunction "PA5_11") (pintype "bidirectional"))
    )
    (net (code "13") (name "B_CV") (class "Default")
      (node (ref "C23") (pin "2") (pinfunction "2_2") (pintype "passive"))
      (node (ref "R7") (pin "1") (pinfunction "1_1") (pintype "passive"))
      (node (ref "U1") (pin "7") (pinfunction "PA1_7") (pintype "bidirectional"))
      (node (ref "U2") (pin "8") (pinfunction "OUT_8") (pintype "output"))
    )
    (net (code "14") (name "B_CV_IN") (class "Default")
      (node (ref "J5") (pin "P3") (pinfunction "3_P3") (pintype "passive"))
      (node (ref "R25") (pin "2") (pinfunction "2_2") (pintype "passive"))
    )
    (net (code "15") (name "B_GATE") (class "Default")
      (node (ref "R12") (pin "2") (pinfunction "2_2") (pintype "passive"))
      (node (ref "U1") (pin "21") (pinfunction "PA11_21") (pintype "bidirectional"))
    )
    (net (code "16") (name "B_TRIG") (class "Default")
      (node (ref "Q3") (pin "C") (pinfunction "C_C") (pintype "passive"))
      (node (ref "U1") (pin "14") (pinfunction "PB0_14") (pintype "bidirectional"))
    )
    (net (code "17") (name "B_TRIG_IN") (class "Default")
      (node (ref "J2") (pin "P3") (pinfunction "3_P3") (pintype "passive"))
      (node (ref "R19") (pin "1") (pinfunction "1_1") (pintype "passive"))
    )
    (net (code "18") (name "C_ADC") (class "Default")
      (node (ref "R34") (pin "2") (pinfunction "2_2") (pintype "passive"))
      (node (ref "U1") (pin "12") (pinfunction "PA6_12") (pintype "bidirectional"))
    )
    (net (code "19") (name "C_CV") (class "Default")
      (node (ref "C24") (pin "2") (pinfunction "2_2") (pintype "passive"))
      (node (ref "R8") (pin "1") (pinfunction "1_1") (pintype "passive"))
      (node (ref "U1") (pin "8") (pinfunction "PA2_8") (pintype "bidirectional"))
      (node (ref "U2") (pin "14") (pinfunction "OUT_14") (pintype "output"))
    )
    (net (code "20") (name "C_GATE") (class "Default")
      (node (ref "R11") (pin "2") (pinfunction "2_2") (pintype "passive"))
      (node (ref "U1") (pin "22") (pinfunction "PA12_22") (pintype "bidirectional"))
    )
    (net (code "21") (name "C_TRIG") (class "Default")
      (node (ref "Q2") (pin "C") (pinfunction "C_C") (pintype "passive"))
      (node (ref "U1") (pin "15") (pinfunction "PB1_15") (pintype "bidirectional"))
    )
    (net (code "22") (name "C_TRIG_IN") (class "Default")
      (node (ref "J1") (pin "P3") (pinfunction "3_P3") (pintype "passive"))
      (node (ref "R18") (pin "1") (pinfunction "1_1") (pintype "passive"))
    )
    (net (code "23") (name "GND") (class "Default")
      (node (ref "C1") (pin "2") (pinfunction "2_2") (pintype "passive"))
      (node (ref "C10") (pin "1") (pinfunction "1_1") (pintype "passive"))
      (node (ref "C11") (pin "2") (pinfunction "2_2") (pintype "passive"))
      (node (ref "C12") (pin "2") (pinfunction "2_2") (pintype "passive"))
      (node (ref "C13") (pin "2") (pinfunction "2_2") (pintype "passive"))
      (node (ref "C14") (pin "2") (pinfunction "2_2") (pintype "passive"))
      (node (ref "C15") (pin "2") (pinfunction "2_2") (pintype "passive"))
      (node (ref "C16") (pin "2") (pinfunction "2_2") (pintype "passive"))
      (node (ref "C17") (pin "2") (pinfunction "2_2") (pintype "passive"))
      (node (ref "C18") (pin "2") (pinfunction "2_2") (pintype "passive"))
      (node (ref "C19") (pin "2") (pinfunction "2_2") (pintype "passive"))
      (node (ref "C2") (pin "2") (pinfunction "2_2") (pintype "passive"))
      (node (ref "C20") (pin "2") (pinfunction "2_2") (pintype "passive"))
      (node (ref "C21") (pin "1") (pinfunction "1_1") (pintype "passive"))
      (node (ref "C22") (pin "1") (pinfunction "1_1") (pintype "passive"))
      (node (ref "C25") (pin "1") (pinfunction "1_1") (pintype "passive"))
      (node (ref "C26") (pin "2") (pinfunction "2_2") (pintype "passive"))
      (node (ref "C27") (pin "2") (pinfunction "2_2") (pintype "passive"))
      (node (ref "C28") (pin "2") (pinfunction "2_2") (pintype "passive"))
      (node (ref "C29") (pin "2") (pinfunction "2_2") (pintype "passive"))
      (node (ref "C3") (pin "2") (pinfunction "2_2") (pintype "passive"))
      (node (ref "C31") (pin "2") (pinfunction "2_2") (pintype "passive"))
      (node (ref "C35") (pin "2") (pinfunction "2_2") (pintype "passive"))
      (node (ref "C4") (pin "2") (pinfunction "2_2") (pintype "passive"))
      (node (ref "C5") (pin "2") (pinfunction "2_2") (pintype "passive"))
      (node (ref "C6") (pin "2") (pinfunction "2_2") (pintype "passive"))
      (node (ref "C7") (pin "2") (pinfunction "2_2") (pintype "passive"))
      (node (ref "C8") (pin "-") (pinfunction "-_-") (pintype "passive"))
      (node (ref "C9") (pin "1") (pinfunction "1_1") (pintype "passive"))
      (node (ref "D3") (pin "A") (pinfunction "A_A") (pintype "passive"))
      (node (ref "D4") (pin "A") (pinfunction "A_A") (pintype "passive"))
      (node (ref "D5") (pin "A") (pinfunction "A_A") (pintype "passive"))
      (node (ref "IC1") (pin "2") (pinfunction "GND_2") (pintype "passive"))
      (node (ref "IC2") (pin "2") (pinfunction "GND_2") (pintype "passive"))
      (node (ref "IC3") (pin "1") (pinfunction "C_1") (pintype "passive"))
      (node (ref "IC4") (pin "6") (pinfunction "INH_6") (pintype "input"))
      (node (ref "IC4") (pin "7") (pinfunction "VEE_7") (pintype "power_in"))
      (node (ref "IC4") (pin "8") (pinfunction "GND_8") (pintype "power_in"))
      (node (ref "IC5") (pin "1") (pinfunction "GND_1") (pintype "bidirectional"))
      (node (ref "IC5") (pin "21") (pinfunction "BLANK_21") (pintype "bidirectional"))
      (node (ref "IC6") (pin "11") (pinfunction "V-_11") (pintype "power_in"))
      (node (ref "IC6") (pin "12") (pinfunction "+IN_12") (pintype "input"))
      (node (ref "J1") (pin "P1") (pinfunction "1_P1") (pintype "passive"))
      (node (ref "J1") (pin "P2") (pinfunction "2_P2") (pintype "passive"))
      (node (ref "J10") (pin "P1") (pinfunction "1_P1") (pintype "passive"))
      (node (ref "J11") (pin "P1") (pinfunction "1_P1") (pintype "passive"))
      (node (ref "J12") (pin "P1") (pinfunction "1_P1") (pintype "passive"))
      (node (ref "J2") (pin "P1") (pinfunction "1_P1") (pintype "passive"))
      (node (ref "J2") (pin "P2") (pinfunction "2_P2") (pintype "passive"))
      (node (ref "J3") (pin "P1") (pinfunction "1_P1") (pintype "passive"))
      (node (ref "J3") (pin "P2") (pinfunction "2_P2") (pintype "passive"))
      (node (ref "J4") (pin "P1") (pinfunction "1_P1") (pintype "passive"))
      (node (ref "J4") (pin "P2") (pinfunction "2_P2") (pintype "passive"))
      (node (ref "J5") (pin "P1") (pinfunction "1_P1") (pintype "passive"))
      (node (ref "J5") (pin "P2") (pinfunction "2_P2") (pintype "passive"))
      (node (ref "J6") (pin "P1") (pinfunction "1_P1") (pintype "passive"))
      (node (ref "J6") (pin "P2") (pinfunction "2_P2") (pintype "passive"))
      (node (ref "J7") (pin "P1") (pinfunction "1_P1") (pintype "passive"))
      (node (ref "J8") (pin "P1") (pinfunction "1_P1") (pintype "passive"))
      (node (ref "J9") (pin "P1") (pinfunction "1_P1") (pintype "passive"))
      (node (ref "JP1") (pin "3") (pinfunction "3_3") (pintype "passive"))
      (node (ref "JP1") (pin "4") (pinfunction "4_4") (pintype "passive"))
      (node (ref "JP1") (pin "5") (pinfunction "5_5") (pintype "passive"))
      (node (ref "JP1") (pin "6") (pinfunction "6_6") (pintype "passive"))
      (node (ref "JP1") (pin "7") (pinfunction "7_7") (pintype "passive"))
      (node (ref "JP1") (pin "8") (pinfunction "8_8") (pintype "passive"))
      (node (ref "JP2") (pin "1") (pinfunction "1_1") (pintype "passive"))
      (node (ref "POT_A") (pin "P$3") (pinfunction "A_P$3") (pintype "passive"))
      (node (ref "POT_B") (pin "P$3") (pinfunction "A_P$3") (pintype "passive"))
      (node (ref "POT_C") (pin "P$3") (pinfunction "A_P$3") (pintype "passive"))
      (node (ref "Q1") (pin "2") (pinfunction "LID1_2") (pintype "power_in"))
      (node (ref "Q1") (pin "4") (pinfunction "LID2_4") (pintype "power_in"))
      (node (ref "Q2") (pin "E") (pinfunction "E_E") (pintype "passive"))
      (node (ref "Q3") (pin "E") (pinfunction "E_E") (pintype "passive"))
      (node (ref "Q4") (pin "E") (pinfunction "E_E") (pintype "passive"))
      (node (ref "R20") (pin "1") (pinfunction "1_1") (pintype "passive"))
      (node (ref "R21") (pin "1") (pinfunction "1_1") (pintype "passive"))
      (node (ref "R23") (pin "1") (pinfunction "1_1") (pintype "passive"))
      (node (ref "R45") (pin "2") (pinfunction "2_2") (pintype "passive"))
      (node (ref "R46") (pin "2") (pinfunction "2_2") (pintype "passive"))
      (node (ref "R47") (pin "2") (pinfunction "2_2") (pintype "passive"))
      (node (ref "R5") (pin "2") (pinfunction "2_2") (pintype "passive"))
      (node (ref "SLD_A") (pin "1") (pinfunction "A_1") (pintype "passive"))
      (node (ref "SLD_B") (pin "1") (pinfunction "A_1") (pintype "passive"))
      (node (ref "SLD_C") (pin "1") (pinfunction "A_1") (pintype "passive"))
      (node (ref "SW_A") (pin "1") (pinfunction "1_1") (pintype "passive"))
      (node (ref "SW_A") (pin "2") (pinfunction "2_2") (pintype "passive"))
      (node (ref "SW_B") (pin "1") (pinfunction "1_1") (pintype "passive"))
      (node (ref "SW_B") (pin "2") (pinfunction "2_2") (pintype "passive"))
      (node (ref "SW_C") (pin "1") (pinfunction "1_1") (pintype "passive"))
      (node (ref "SW_C") (pin "2") (pinfunction "2_2") (pintype "passive"))
      (node (ref "U$1") (pin "6") (pinfunction "P$6_6") (pintype "bidirectional"))
      (node (ref "U1") (pin "16") (pinfunction "VSS_2_16") (pintype "power_in"))
      (node (ref "U1") (pin "31") (pinfunction "BOOT0_31") (pintype "input"))
      (node (ref "U1") (pin "32") (pinfunction "VSS_1_32") (pintype "power_in"))
      (node (ref "U2") (pin "10") (pinfunction "+IN_10") (pintype "input"))
      (node (ref "U2") (pin "11") (pinfunction "V-_11") (pintype "power_in"))
      (node (ref "U2") (pin "12") (pinfunction "+IN_12") (pintype "input"))
      (node (ref "U2") (pin "3") (pinfunction "+IN_3") (pintype "input"))
      (node (ref "U2") (pin "5") (pinfunction "+IN_5") (pintype "input"))
      (node (ref "U3") (pin "10") (pinfunction "+IN_10") (pintype "input"))
      (node (ref "U3") (pin "12") (pinfunction "+IN_12") (pintype "input"))
      (node (ref "U3") (pin "3") (pinfunction "+IN_3") (pintype "input"))
      (node (ref "U3") (pin "5") (pinfunction "+IN_5") (pintype "input"))
    )
    (net (code "24") (name "LEDS_SCK") (class "Default")
      (node (ref "IC5") (pin "3") (pinfunction "SCLK_3") (pintype "bidirectional"))
      (node (ref "U1") (pin "26") (pinfunction "PB3_26") (pintype "bidirectional"))
    )
    (net (code "25") (name "LEDS_SIN") (class "Default")
      (node (ref "IC5") (pin "2") (pinfunction "SIN_2") (pintype "bidirectional"))
      (node (ref "U1") (pin "28") (pinfunction "PB5_28") (pintype "bidirectional"))
    )
    (net (code "26") (name "N_U") (class "Default")
      (node (ref "U2") (pin "6") (pinfunction "-IN_6") (pintype "input"))
      (node (ref "U2") (pin "7") (pinfunction "OUT_7") (pintype "output"))
    )
    (net (code "27") (name "Net-(C1-Pad1)") (class "Default")
      (node (ref "C1") (pin "1") (pinfunction "1_1") (pintype "passive"))
      (node (ref "D1") (pin "C") (pinfunction "C_C") (pintype "passive"))
      (node (ref "L1") (pin "1") (pinfunction "1_1") (pintype "passive"))
      (node (ref "L2") (pin "2") (pinfunction "2_2") (pintype "passive"))
      (node (ref "L3") (pin "2") (pinfunction "2_2") (pintype "passive"))
    )
    (net (code "28") (name "Net-(C22-Pad2)") (class "Default")
      (node (ref "C22") (pin "2") (pinfunction "2_2") (pintype "passive"))
      (node (ref "Q1") (pin "1") (pinfunction "1_1") (pintype "passive"))
      (node (ref "R6") (pin "2") (pinfunction "2_2") (pintype "passive"))
    )
    (net (code "29") (name "Net-(D2-PadA)") (class "Default")
      (node (ref "D2") (pin "A") (pinfunction "A_A") (pintype "passive"))
      (node (ref "L4") (pin "2") (pinfunction "2_2") (pintype "passive"))
    )
    (net (code "30") (name "Net-(D3-PadC)") (class "Default")
      (node (ref "D3") (pin "C") (pinfunction "C_C") (pintype "passive"))
      (node (ref "Q2") (pin "B") (pinfunction "B_B") (pintype "passive"))
      (node (ref "R18") (pin "2") (pinfunction "2_2") (pintype "passive"))
      (node (ref "R23") (pin "2") (pinfunction "2_2") (pintype "passive"))
    )
    (net (code "31") (name "Net-(D4-PadC)") (class "Default")
      (node (ref "D4") (pin "C") (pinfunction "C_C") (pintype "passive"))
      (node (ref "Q3") (pin "B") (pinfunction "B_B") (pintype "passive"))
      (node (ref "R19") (pin "2") (pinfunction "2_2") (pintype "passive"))
      (node (ref "R20") (pin "2") (pinfunction "2_2") (pintype "passive"))
    )
    (net (code "32") (name "Net-(D5-PadC)") (class "Default")
      (node (ref "D5") (pin "C") (pinfunction "C_C") (pintype "passive"))
      (node (ref "Q4") (pin "B") (pinfunction "B_B") (pintype "passive"))
      (node (ref "R21") (pin "2") (pinfunction "2_2") (pintype "passive"))
      (node (ref "R22") (pin "2") (pinfunction "2_2") (pintype "passive"))
    )
    (net (code "33") (name "Net-(IC1-VI)") (class "Default")
      (node (ref "C5") (pin "1") (pinfunction "1_1") (pintype "passive"))
      (node (ref "IC1") (pin "1") (pinfunction "VI_1") (pintype "input"))
      (node (ref "L1") (pin "2") (pinfunction "2_2") (pintype "passive"))
    )
    (net (code "34") (name "Net-(IC2-VI)") (class "Default")
      (node (ref "C3") (pin "1") (pinfunction "1_1") (pintype "passive"))
      (node (ref "IC2") (pin "3") (pinfunction "VI_3") (pintype "input"))
      (node (ref "L2") (pin "1") (pinfunction "1_1") (pintype "passive"))
    )
    (net (code "35") (name "Net-(IC4A-X0)") (class "Default")
      (node (ref "IC4") (pin "13") (pinfunction "X0_13") (pintype "bidirectional"))
      (node (ref "POT_C") (pin "P$2") (pinfunction "S_P$2") (pintype "passive"))
    )
    (net (code "36") (name "Net-(IC4A-X1)") (class "Default")
      (node (ref "IC4") (pin "14") (pinfunction "X1_14") (pintype "bidirectional"))
      (node (ref "SLD_C") (pin "2") (pinfunction "S_2") (pintype "passive"))
    )
    (net (code "37") (name "Net-(IC4A-X2)") (class "Default")
      (node (ref "IC4") (pin "15") (pinfunction "X2_15") (pintype "bidirectional"))
      (node (ref "SLD_B") (pin "2") (pinfunction "S_2") (pintype "passive"))
    )
    (net (code "38") (name "Net-(IC4A-X3)") (class "Default")
      (node (ref "IC4") (pin "12") (pinfunction "X3_12") (pintype "bidirectional"))
      (node (ref "POT_A") (pin "P$2") (pinfunction "S_P$2") (pintype "passive"))
    )
    (net (code "39") (name "Net-(IC4A-X4)") (class "Default")
      (node (ref "IC4") (pin "1") (pinfunction "X4_1") (pintype "bidirectional"))
      (node (ref "SLD_A") (pin "2") (pinfunction "S_2") (pintype "passive"))
    )
    (net (code "40") (name "Net-(IC4A-X6)") (class "Default")
      (node (ref "IC4") (pin "2") (pinfunction "X6_2") (pintype "bidirectional"))
      (node (ref "POT_B") (pin "P$2") (pinfunction "S_P$2") (pintype "passive"))
    )
    (net (code "41") (name "Net-(IC5-IREF)") (class "Default")
      (node (ref "IC5") (pin "23") (pinfunction "IREF_23") (pintype "bidirectional"))
      (node (ref "R5") (pin "1") (pinfunction "1_1") (pintype "passive"))
    )
    (net (code "42") (name "Net-(IC5-OUT1)") (class "Default")
      (node (ref "IC5") (pin "6") (pinfunction "OUT1_6") (pintype "bidirectional"))
      (node (ref "R15") (pin "2") (pinfunction "2_2") (pintype "passive"))
    )
    (net (code "43") (name "Net-(IC5-OUT2)") (class "Default")
      (node (ref "IC5") (pin "7") (pinfunction "OUT2_7") (pintype "bidirectional"))
      (node (ref "MODE_C") (pin "RED_C") (pinfunction "RED_RED_C") (pintype "bidirectional"))
    )
    (net (code "44") (name "Net-(IC5-OUT3)") (class "Default")
      (node (ref "IC5") (pin "8") (pinfunction "OUT3_8") (pintype "bidirectional"))
      (node (ref "MODE_C") (pin "GREEN_C") (pinfunction "GRN_GREEN_C") (pintype "bidirectional"))
    )
    (net (code "45") (name "Net-(IC5-OUT4)") (class "Default")
      (node (ref "IC5") (pin "9") (pinfunction "OUT4_9") (pintype "bidirectional"))
      (node (ref "MODE_A") (pin "GREEN_C") (pinfunction "GRN_GREEN_C") (pintype "bidirectional"))
    )
    (net (code "46") (name "Net-(IC5-OUT5)") (class "Default")
      (node (ref "IC5") (pin "10") (pinfunction "OUT5_10") (pintype "bidirectional"))
      (node (ref "MODE_A") (pin "RED_C") (pinfunction "RED_RED_C") (pintype "bidirectional"))
    )
    (net (code "47") (name "Net-(IC5-OUT6)") (class "Default")
      (node (ref "IC5") (pin "11") (pinfunction "OUT6_11") (pintype "bidirectional"))
      (node (ref "MODE_B") (pin "GREEN_C") (pinfunction "GRN_GREEN_C") (pintype "bidirectional"))
    )
    (net (code "48") (name "Net-(IC5-OUT7)") (class "Default")
      (node (ref "IC5") (pin "12") (pinfunction "OUT7_12") (pintype "bidirectional"))
      (node (ref "MODE_B") (pin "RED_C") (pinfunction "RED_RED_C") (pintype "bidirectional"))
    )
    (net (code "49") (name "Net-(IC5-OUT8)") (class "Default")
      (node (ref "IC5") (pin "13") (pinfunction "OUT8_13") (pintype "bidirectional"))
      (node (ref "LED1") (pin "GREEN_C") (pinfunction "GRN_GREEN_C") (pintype "bidirectional"))
    )
    (net (code "50") (name "Net-(IC5-OUT9)") (class "Default")
      (node (ref "IC5") (pin "14") (pinfunction "OUT9_14") (pintype "bidirectional"))
      (node (ref "LED1") (pin "RED_C") (pinfunction "RED_RED_C") (pintype "bidirectional"))
    )
    (net (code "51") (name "Net-(IC5-OUT10)") (class "Default")
      (node (ref "IC5") (pin "15") (pinfunction "OUT10_15") (pintype "bidirectional"))
      (node (ref "LED2") (pin "RED_C") (pinfunction "RED_RED_C") (pintype "bidirectional"))
    )
    (net (code "52") (name "Net-(IC5-OUT11)") (class "Default")
      (node (ref "IC5") (pin "16") (pinfunction "OUT11_16") (pintype "bidirectional"))
      (node (ref "LED2") (pin "GREEN_C") (pinfunction "GRN_GREEN_C") (pintype "bidirectional"))
    )
    (net (code "53") (name "Net-(IC5-OUT12)") (class "Default")
      (node (ref "IC5") (pin "17") (pinfunction "OUT12_17") (pintype "bidirectional"))
      (node (ref "LED3") (pin "RED_C") (pinfunction "RED_RED_C") (pintype "bidirectional"))
    )
    (net (code "54") (name "Net-(IC5-OUT13)") (class "Default")
      (node (ref "IC5") (pin "18") (pinfunction "OUT13_18") (pintype "bidirectional"))
      (node (ref "LED3") (pin "GREEN_C") (pinfunction "GRN_GREEN_C") (pintype "bidirectional"))
    )
    (net (code "55") (name "Net-(IC5-OUT14)") (class "Default")
      (node (ref "IC5") (pin "19") (pinfunction "OUT14_19") (pintype "bidirectional"))
      (node (ref "R16") (pin "2") (pinfunction "2_2") (pintype "passive"))
    )
    (net (code "56") (name "Net-(IC5-OUT15)") (class "Default")
      (node (ref "IC5") (pin "20") (pinfunction "OUT15_20") (pintype "bidirectional"))
      (node (ref "R17") (pin "2") (pinfunction "2_2") (pintype "passive"))
    )
    (net (code "57") (name "Net-(IC5-VCC)") (class "Default")
      (node (ref "C14") (pin "1") (pinfunction "1_1") (pintype "passive"))
      (node (ref "C15") (pin "1") (pinfunction "1_1") (pintype "passive"))
      (node (ref "IC5") (pin "24") (pinfunction "VCC_24") (pintype "bidirectional"))
      (node (ref "L5") (pin "1") (pinfunction "1_1") (pintype "passive"))
    )
    (net (code "58") (name "Net-(IC6A-+IN)") (class "Default")
      (node (ref "IC6") (pin "3") (pinfunction "+IN_3") (pintype "input"))
      (node (ref "R44") (pin "2") (pinfunction "2_2") (pintype "passive"))
      (node (ref "R47") (pin "1") (pinfunction "1_1") (pintype "passive"))
    )
    (net (code "59") (name "Net-(IC6A--IN)") (class "Default")
      (node (ref "IC6") (pin "2") (pinfunction "-IN_2") (pintype "input"))
      (node (ref "R13") (pin "1") (pinfunction "1_1") (pintype "passive"))
    )
    (net (code "60") (name "Net-(IC6A-OUT)") (class "Default")
      (node (ref "IC6") (pin "1") (pinfunction "OUT_1") (pintype "output"))
      (node (ref "R39") (pin "2") (pinfunction "2_2") (pintype "passive"))
      (node (ref "R44") (pin "1") (pinfunction "1_1") (pintype "passive"))
    )
    (net (code "61") (name "Net-(IC6B-+IN)") (class "Default")
      (node (ref "IC6") (pin "5") (pinfunction "+IN_5") (pintype "input"))
      (node (ref "R41") (pin "2") (pinfunction "2_2") (pintype "passive"))
      (node (ref "R46") (pin "1") (pinfunction "1_1") (pintype "passive"))
    )
    (net (code "62") (name "Net-(IC6B--IN)") (class "Default")
      (node (ref "IC6") (pin "6") (pinfunction "-IN_6") (pintype "input"))
      (node (ref "R12") (pin "1") (pinfunction "1_1") (pintype "passive"))
    )
    (net (code "63") (name "Net-(IC6B-OUT)") (class "Default")
      (node (ref "IC6") (pin "7") (pinfunction "OUT_7") (pintype "output"))
      (node (ref "R38") (pin "2") (pinfunction "2_2") (pintype "passive"))
      (node (ref "R41") (pin "1") (pinfunction "1_1") (pintype "passive"))
    )
    (net (code "64") (name "Net-(IC6C-+IN)") (class "Default")
      (node (ref "IC6") (pin "10") (pinfunction "+IN_10") (pintype "input"))
      (node (ref "R36") (pin "2") (pinfunction "2_2") (pintype "passive"))
      (node (ref "R45") (pin "1") (pinfunction "1_1") (pintype "passive"))
    )
    (net (code "65") (name "Net-(IC6C--IN)") (class "Default")
      (node (ref "IC6") (pin "9") (pinfunction "-IN_9") (pintype "input"))
      (node (ref "R11") (pin "1") (pinfunction "1_1") (pintype "passive"))
    )
    (net (code "66") (name "Net-(IC6C-OUT)") (class "Default")
      (node (ref "IC6") (pin "8") (pinfunction "OUT_8") (pintype "output"))
      (node (ref "R36") (pin "1") (pinfunction "1_1") (pintype "passive"))
      (node (ref "R37") (pin "2") (pinfunction "2_2") (pintype "passive"))
    )
    (net (code "67") (name "Net-(IC6D--IN)") (class "Default")
      (node (ref "IC6") (pin "13") (pinfunction "-IN_13") (pintype "input"))
      (node (ref "IC6") (pin "14") (pinfunction "OUT_14") (pintype "output"))
    )
    (net (code "68") (name "Net-(J4-3)") (class "Default")
      (node (ref "J4") (pin "P3") (pinfunction "3_P3") (pintype "passive"))
      (node (ref "R24") (pin "2") (pinfunction "2_2") (pintype "passive"))
    )
    (net (code "69") (name "Net-(J6-3)") (class "Default")
      (node (ref "J6") (pin "P3") (pinfunction "3_P3") (pintype "passive"))
      (node (ref "R26") (pin "2") (pinfunction "2_2") (pintype "passive"))
    )
    (net (code "70") (name "Net-(J7-3)") (class "Default")
      (node (ref "J7") (pin "P3") (pinfunction "3_P3") (pintype "passive"))
      (node (ref "R37") (pin "1") (pinfunction "1_1") (pintype "passive"))
    )
    (net (code "71") (name "Net-(J8-3)") (class "Default")
      (node (ref "J8") (pin "P3") (pinfunction "3_P3") (pintype "passive"))
      (node (ref "R38") (pin "1") (pinfunction "1_1") (pintype "passive"))
    )
    (net (code "72") (name "Net-(J9-3)") (class "Default")
      (node (ref "J9") (pin "P3") (pinfunction "3_P3") (pintype "passive"))
      (node (ref "R39") (pin "1") (pinfunction "1_1") (pintype "passive"))
    )
    (net (code "73") (name "Net-(J10-3)") (class "Default")
      (node (ref "J10") (pin "P3") (pinfunction "3_P3") (pintype "passive"))
      (node (ref "R35") (pin "1") (pinfunction "1_1") (pintype "passive"))
      (node (ref "R40") (pin "1") (pinfunction "1_1") (pintype "passive"))
    )
    (net (code "74") (name "Net-(J11-3)") (class "Default")
      (node (ref "J11") (pin "P3") (pinfunction "3_P3") (pintype "passive"))
      (node (ref "R29") (pin "1") (pinfunction "1_1") (pintype "passive"))
      (node (ref "R42") (pin "1") (pinfunction "1_1") (pintype "passive"))
    )
    (net (code "75") (name "Net-(J12-3)") (class "Default")
      (node (ref "J12") (pin "P3") (pinfunction "3_P3") (pintype "passive"))
      (node (ref "R32") (pin "1") (pinfunction "1_1") (pintype "passive"))
      (node (ref "R43") (pin "1") (pinfunction "1_1") (pintype "passive"))
    )
    (net (code "76") (name "Net-(Q1B-2)") (class "Default")
      (node (ref "C21") (pin "2") (pinfunction "2_2") (pintype "passive"))
      (node (ref "Q1") (pin "3") (pinfunction "2_3") (pintype "passive"))
      (node (ref "R9") (pin "2") (pinfunction "2_2") (pintype "passive"))
    )
    (net (code "77") (name "Net-(SLD_AA-C)") (class "Default")
      (node (ref "R16") (pin "1") (pinfunction "1_1") (pintype "passive"))
      (node (ref "SLD_A") (pin "E") (pinfunction "C_E") (pintype "passive"))
    )
    (net (code "78") (name "Net-(SLD_BA-C)") (class "Default")
      (node (ref "R17") (pin "1") (pinfunction "1_1") (pintype "passive"))
      (node (ref "SLD_B") (pin "E") (pinfunction "C_E") (pintype "passive"))
    )
    (net (code "79") (name "Net-(SLD_CA-C)") (class "Default")
      (node (ref "R15") (pin "1") (pinfunction "1_1") (pintype "passive"))
      (node (ref "SLD_C") (pin "E") (pinfunction "C_E") (pintype "passive"))
    )
    (net (code "80") (name "Net-(U1-PF0{slash}OSC_IN)") (class "Default")
      (node (ref "R9") (pin "1") (pinfunction "1_1") (pintype "passive"))
      (node (ref "U1") (pin "2") (pinfunction "PF0/OSC_IN_2") (pintype "bidirectional"))
    )
    (net (code "81") (name "Net-(U1-PF1{slash}OSC_OUT)") (class "Default")
      (node (ref "R6") (pin "1") (pinfunction "1_1") (pintype "passive"))
      (node (ref "U1") (pin "3") (pinfunction "PF1/OSC_OUT_3") (pintype "bidirectional"))
    )
    (net (code "82") (name "Net-(U2A--IN)") (class "Default")
      (node (ref "C30") (pin "1") (pinfunction "1_1") (pintype "passive"))
      (node (ref "R14") (pin "2") (pinfunction "2_2") (pintype "passive"))
      (node (ref "R2") (pin "1") (pinfunction "1_1") (pintype "passive"))
      (node (ref "R26") (pin "1") (pinfunction "1_1") (pintype "passive"))
      (node (ref "U2") (pin "2") (pinfunction "-IN_2") (pintype "input"))
    )
    (net (code "83") (name "Net-(U2C--IN)") (class "Default")
      (node (ref "C23") (pin "1") (pinfunction "1_1") (pintype "passive"))
      (node (ref "R25") (pin "1") (pinfunction "1_1") (pintype "passive"))
      (node (ref "R3") (pin "1") (pinfunction "1_1") (pintype "passive"))
      (node (ref "R7") (pin "2") (pinfunction "2_2") (pintype "passive"))
      (node (ref "U2") (pin "9") (pinfunction "-IN_9") (pintype "input"))
    )
    (net (code "84") (name "Net-(U2D--IN)") (class "Default")
      (node (ref "C24") (pin "1") (pinfunction "1_1") (pintype "passive"))
      (node (ref "R24") (pin "1") (pinfunction "1_1") (pintype "passive"))
      (node (ref "R4") (pin "1") (pinfunction "1_1") (pintype "passive"))
      (node (ref "R8") (pin "2") (pinfunction "2_2") (pintype "passive"))
      (node (ref "U2") (pin "13") (pinfunction "-IN_13") (pintype "input"))
    )
    (net (code "85") (name "Net-(U3A--IN)") (class "Default")
      (node (ref "C33") (pin "1") (pinfunction "1_1") (pintype "passive"))
      (node (ref "R30") (pin "1") (pinfunction "1_1") (pintype "passive"))
      (node (ref "R31") (pin "1") (pinfunction "1_1") (pintype "passive"))
      (node (ref "R32") (pin "2") (pinfunction "2_2") (pintype "passive"))
      (node (ref "U3") (pin "2") (pinfunction "-IN_2") (pintype "input"))
    )
    (net (code "86") (name "Net-(U3A-OUT)") (class "Default")
      (node (ref "C33") (pin "2") (pinfunction "2_2") (pintype "passive"))
      (node (ref "R43") (pin "2") (pinfunction "2_2") (pintype "passive"))
      (node (ref "U3") (pin "1") (pinfunction "OUT_1") (pintype "output"))
    )
    (net (code "87") (name "Net-(U3B--IN)") (class "Default")
      (node (ref "C32") (pin "1") (pinfunction "1_1") (pintype "passive"))
      (node (ref "R27") (pin "1") (pinfunction "1_1") (pintype "passive"))
      (node (ref "R28") (pin "1") (pinfunction "1_1") (pintype "passive"))
      (node (ref "R29") (pin "2") (pinfunction "2_2") (pintype "passive"))
      (node (ref "U3") (pin "6") (pinfunction "-IN_6") (pintype "input"))
    )
    (net (code "88") (name "Net-(U3B-OUT)") (class "Default")
      (node (ref "C32") (pin "2") (pinfunction "2_2") (pintype "passive"))
      (node (ref "R42") (pin "2") (pinfunction "2_2") (pintype "passive"))
      (node (ref "U3") (pin "7") (pinfunction "OUT_7") (pintype "output"))
    )
    (net (code "89") (name "Net-(U3C--IN)") (class "Default")
      (node (ref "C34") (pin "1") (pinfunction "1_1") (pintype "passive"))
      (node (ref "R33") (pin "1") (pinfunction "1_1") (pintype "passive"))
      (node (ref "R34") (pin "1") (pinfunction "1_1") (pintype "passive"))
      (node (ref "R35") (pin "2") (pinfunction "2_2") (pintype "passive"))
      (node (ref "U3") (pin "9") (pinfunction "-IN_9") (pintype "input"))
    )
    (net (code "90") (name "Net-(U3C-OUT)") (class "Default")
      (node (ref "C34") (pin "2") (pinfunction "2_2") (pintype "passive"))
      (node (ref "R40") (pin "2") (pinfunction "2_2") (pintype "passive"))
      (node (ref "U3") (pin "8") (pinfunction "OUT_8") (pintype "output"))
    )
    (net (code "91") (name "Net-(U3D--IN)") (class "Default")
      (node (ref "U3") (pin "13") (pinfunction "-IN_13") (pintype "input"))
      (node (ref "U3") (pin "14") (pinfunction "OUT_14") (pintype "output"))
    )
    (net (code "92") (name "POTS_ADDR_A") (class "Default")
      (node (ref "IC4") (pin "11") (pinfunction "A_11") (pintype "input"))
      (node (ref "U1") (pin "13") (pinfunction "PA7_13") (pintype "bidirectional"))
    )
    (net (code "93") (name "POTS_ADDR_B") (class "Default")
      (node (ref "IC4") (pin "10") (pinfunction "B_10") (pintype "input"))
      (node (ref "U1") (pin "18") (pinfunction "PA8_18") (pintype "bidirectional"))
    )
    (net (code "94") (name "POTS_ADDR_C") (class "Default")
      (node (ref "IC4") (pin "9") (pinfunction "C_9") (pintype "input"))
      (node (ref "U1") (pin "19") (pinfunction "PA9_19") (pintype "bidirectional"))
    )
    (net (code "95") (name "RESET") (class "Default")
      (node (ref "C28") (pin "1") (pinfunction "1_1") (pintype "passive"))
      (node (ref "JP2") (pin "4") (pinfunction "4_4") (pintype "passive"))
      (node (ref "R10") (pin "2") (pinfunction "2_2") (pintype "passive"))
      (node (ref "U1") (pin "4") (pinfunction "NRST_4") (pintype "bidirectional"))
    )
    (net (code "96") (name "SWCLK") (class "Default")
      (node (ref "JP2") (pin "3") (pinfunction "3_3") (pintype "passive"))
      (node (ref "U1") (pin "24") (pinfunction "PA14_24") (pintype "bidirectional"))
    )
    (net (code "97") (name "SWDIO") (class "Default")
      (node (ref "JP2") (pin "2") (pinfunction "2_2") (pintype "passive"))
      (node (ref "U1") (pin "23") (pinfunction "PA13_23") (pintype "bidirectional"))
    )
    (net (code "98") (name "SW_MODE_A") (class "Default")
      (node (ref "SW_A") (pin "3") (pinfunction "3_3") (pintype "passive"))
      (node (ref "SW_A") (pin "4") (pinfunction "4_4") (pintype "passive"))
      (node (ref "U1") (pin "27") (pinfunction "PB4_27") (pintype "bidirectional"))
    )
    (net (code "99") (name "SW_MODE_B") (class "Default")
      (node (ref "SW_B") (pin "3") (pinfunction "3_3") (pintype "passive"))
      (node (ref "SW_B") (pin "4") (pinfunction "4_4") (pintype "passive"))
      (node (ref "U1") (pin "29") (pinfunction "PB6_29") (pintype "bidirectional"))
    )
    (net (code "100") (name "SW_MODE_C") (class "Default")
      (node (ref "SW_C") (pin "3") (pinfunction "3_3") (pintype "passive"))
      (node (ref "SW_C") (pin "4") (pinfunction "4_4") (pintype "passive"))
      (node (ref "U1") (pin "30") (pinfunction "PB7_30") (pintype "bidirectional"))
    )
    (net (code "101") (name "VCC") (class "Default")
      (node (ref "C2") (pin "1") (pinfunction "1_1") (pintype "passive"))
      (node (ref "C31") (pin "1") (pinfunction "1_1") (pintype "passive"))
      (node (ref "C35") (pin "1") (pinfunction "1_1") (pintype "passive"))
      (node (ref "C4") (pin "1") (pinfunction "1_1") (pintype "passive"))
      (node (ref "IC6") (pin "4") (pinfunction "V+_4") (pintype "power_in"))
      (node (ref "L3") (pin "1") (pinfunction "1_1") (pintype "passive"))
      (node (ref "U$1") (pin "1") (pinfunction "P$1_1") (pintype "bidirectional"))
      (node (ref "U3") (pin "4") (pinfunction "V+_4") (pintype "power_in"))
    )
    (net (code "102") (name "VEE") (class "Default")
      (node (ref "C10") (pin "2") (pinfunction "2_2") (pintype "passive"))
      (node (ref "C25") (pin "2") (pinfunction "2_2") (pintype "passive"))
      (node (ref "C9") (pin "2") (pinfunction "2_2") (pintype "passive"))
      (node (ref "L4") (pin "1") (pinfunction "1_1") (pintype "passive"))
      (node (ref "R1") (pin "1") (pinfunction "1_1") (pintype "passive"))
      (node (ref "U$1") (pin "2") (pinfunction "P$2_2") (pintype "bidirectional"))
      (node (ref "U3") (pin "11") (pinfunction "V-_11") (pintype "power_in"))
    )
    (net (code "103") (name "unconnected-(IC4A-X5-Pad5)") (class "Default")
      (node (ref "IC4") (pin "5") (pinfunction "X5_5") (pintype "bidirectional"))
    )
    (net (code "104") (name "unconnected-(IC4A-X7-Pad4)") (class "Default")
      (node (ref "IC4") (pin "4") (pinfunction "X7_4") (pintype "bidirectional"))
    )
    (net (code "105") (name "unconnected-(IC5-LAT-Pad4)") (class "Default")
      (node (ref "IC5") (pin "4") (pinfunction "LAT_4") (pintype "bidirectional"))
    )
    (net (code "106") (name "unconnected-(IC5-OUT0-Pad5)") (class "Default")
      (node (ref "IC5") (pin "5") (pinfunction "OUT0_5") (pintype "bidirectional"))
    )
    (net (code "107") (name "unconnected-(IC5-SOUT-Pad22)") (class "Default")
      (node (ref "IC5") (pin "22") (pinfunction "SOUT_22") (pintype "bidirectional"))
    )
    (net (code "108") (name "unconnected-(J7-2-PadP2)") (class "Default")
      (node (ref "J7") (pin "P2") (pinfunction "2_P2") (pintype "passive"))
    )
    (net (code "109") (name "unconnected-(J8-2-PadP2)") (class "Default")
      (node (ref "J8") (pin "P2") (pinfunction "2_P2") (pintype "passive"))
    )
    (net (code "110") (name "unconnected-(J9-2-PadP2)") (class "Default")
      (node (ref "J9") (pin "P2") (pinfunction "2_P2") (pintype "passive"))
    )
    (net (code "111") (name "unconnected-(J10-2-PadP2)") (class "Default")
      (node (ref "J10") (pin "P2") (pinfunction "2_P2") (pintype "passive"))
    )
    (net (code "112") (name "unconnected-(J11-2-PadP2)") (class "Default")
      (node (ref "J11") (pin "P2") (pinfunction "2_P2") (pintype "passive"))
    )
    (net (code "113") (name "unconnected-(J12-2-PadP2)") (class "Default")
      (node (ref "J12") (pin "P2") (pinfunction "2_P2") (pintype "passive"))
    )
  )
)
